# USB-C.net
KiCad netlist of a schematic drawn in Altium Designer
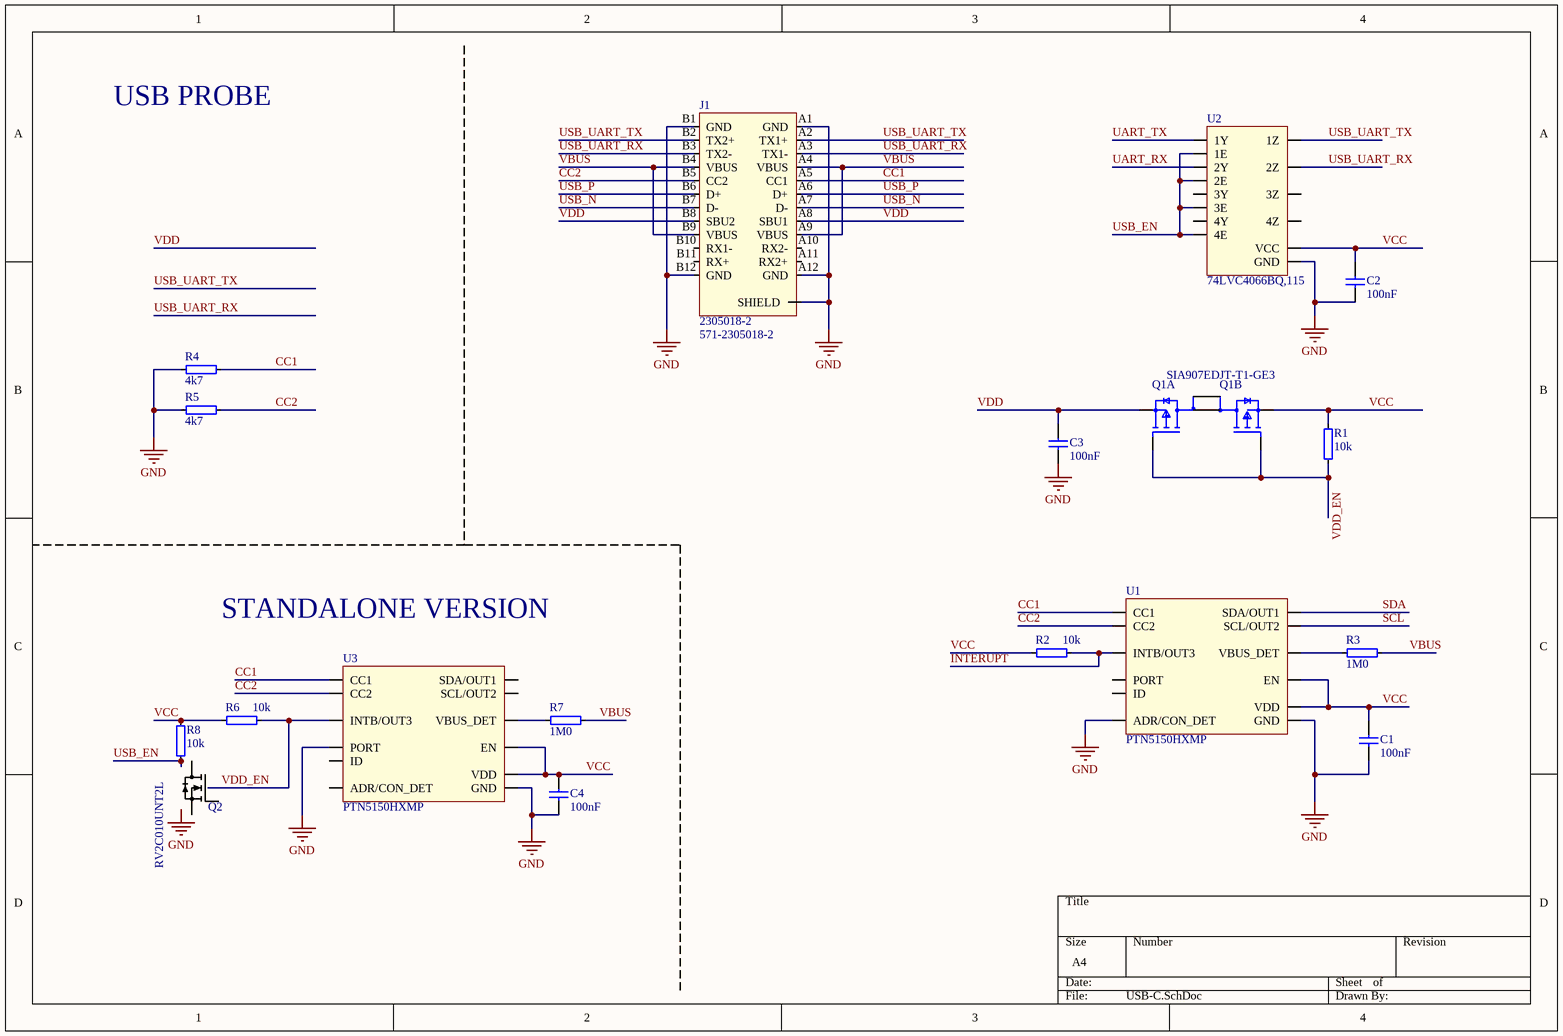
[diagram p0: USB-C.SchDoc]

(export (version "E")
  (design (tool "Eeschema 10.0.6"))
  (components
    (comp (ref "C1")
      (value "100nF")
      (footprint "CAPC0603X03L_C")
      (description "Capacitor, X5R, ±10%")
      (fields (field (name "PART NUMBER") "C0201-100n") (field (name "MANUFACTURER") "N.A."))
      (libsource (lib "main") (part "C0201-100n"))
    )
    (comp (ref "C2")
      (value "100nF")
      (footprint "CAPC0603X03L_C")
      (description "Capacitor, X5R, ±10%")
      (fields (field (name "PART NUMBER") "C0201-100n") (field (name "MANUFACTURER") "N.A."))
      (libsource (lib "main") (part "C0201-100n"))
    )
    (comp (ref "C3")
      (value "100nF")
      (footprint "CAPC0603X03L_C")
      (description "Capacitor, X5R, ±10%")
      (fields (field (name "PART NUMBER") "C0201-100n") (field (name "MANUFACTURER") "N.A."))
      (libsource (lib "main") (part "C0201-100n"))
    )
    (comp (ref "C4")
      (value "100nF")
      (footprint "CAPC0603X03L_C")
      (description "Capacitor, X5R, ±10%")
      (fields (field (name "PART NUMBER") "C0201-100n") (field (name "MANUFACTURER") "N.A."))
      (libsource (lib "main") (part "C0201-100n"))
    )
    (comp (ref "J1")
      (value "2305018-2")
      (footprint "2305018-2")
      (description "Usb 3.1 Type C, 10GBPS, Receptacle, Rigusb Connectors Usb Type C, Rec IPX8 on Board Dual SMT")
      (fields
        (field (name "MANUFACTURER") "TE Connectivity AMP")
        (field (name "SUPPLIER PART NUMBER 1") "571-2305018-2")
      )
      (libsource (lib "Schlib1") (part "2305018-2"))
    )
    (comp (ref "Q1")
      (value "SIA907EDJT-T1-GE3")
      (footprint "FP-C-07431-DUAL-MFG")
      (description "SiA907EDJT Series Dual P Channel 20 V 0.057 Ohm 7.8 W Mosfet - PowerPAK SC-70-6L")
      (fields (field (name "MANUFACTURER") "Vishay Siliconix"))
      (libsource (lib "Schlib1") (part "SIA907EDJT-T1-GE3"))
    )
    (comp (ref "Q2")
      (value "RV2C010UNT2L")
      (footprint "DFN65P100X40-3L")
      (description "MOSFET Transistor, N Channel, 1 A, 20 V, 0.34 ohm, 4.5 V, 1 V RoHS Compliant: Yes")
      (fields (field (name "MANUFACTURER") "Rohm"))
      (libsource (lib "Schlib1") (part "RV2C010UNT2L"))
    )
    (comp (ref "R1")
      (value "10k")
      (footprint "RESC0603X03L_C")
      (description "Resistor, ±1%, 0.05W")
      (fields (field (name "PART NUMBER") "R0201-10k") (field (name "MANUFACTURER") "N.A."))
      (libsource (lib "main") (part "R0201-10k"))
    )
    (comp (ref "R2")
      (value "10k")
      (footprint "RESC0603X03L_C")
      (description "Resistor, ±1%, 0.05W")
      (fields (field (name "PART NUMBER") "R0201-10k") (field (name "MANUFACTURER") "N.A."))
      (libsource (lib "main") (part "R0201-10k"))
    )
    (comp (ref "R3")
      (value "1M0")
      (footprint "RESC0603X03L_C")
      (description "Resistor, ±1%, 0.05W")
      (fields (field (name "PART NUMBER") "R0201-1M0") (field (name "MANUFACTURER") "N.A."))
      (libsource (lib "main") (part "R0201-1M0"))
    )
    (comp (ref "R4")
      (value "4k7")
      (footprint "RESC0603X03L_C")
      (description "Resistor, ±1%, 0.05W")
      (fields (field (name "PART NUMBER") "R0201-4k7") (field (name "MANUFACTURER") "N.A."))
      (libsource (lib "main") (part "R0201-4k7"))
    )
    (comp (ref "R5")
      (value "4k7")
      (footprint "RESC0603X03L_C")
      (description "Resistor, ±1%, 0.05W")
      (fields (field (name "PART NUMBER") "R0201-4k7") (field (name "MANUFACTURER") "N.A."))
      (libsource (lib "main") (part "R0201-4k7"))
    )
    (comp (ref "R6")
      (value "10k")
      (footprint "RESC0603X03L_C")
      (description "Resistor, ±1%, 0.05W")
      (fields (field (name "PART NUMBER") "R0201-10k") (field (name "MANUFACTURER") "N.A."))
      (libsource (lib "main") (part "R0201-10k"))
    )
    (comp (ref "R7")
      (value "1M0")
      (footprint "RESC0603X03L_C")
      (description "Resistor, ±1%, 0.05W")
      (fields (field (name "PART NUMBER") "R0201-1M0") (field (name "MANUFACTURER") "N.A."))
      (libsource (lib "main") (part "R0201-1M0"))
    )
    (comp (ref "R8")
      (value "10k")
      (footprint "RESC0603X03L_C")
      (description "Resistor, ±1%, 0.05W")
      (fields (field (name "PART NUMBER") "R0201-10k") (field (name "MANUFACTURER") "N.A."))
      (libsource (lib "main") (part "R0201-10k"))
    )
    (comp (ref "U1")
      (value "PTN5150HXMP")
      (footprint "PTN5150HXMP")
      (description "Usb Interface IC PTN5150HX/X2QFN12/REEL 13\" Q2/")
      (fields (field (name "MANUFACTURER") "NXP Semiconductors"))
      (libsource (lib "Schlib1") (part "PTN5150HXMP"))
    )
    (comp (ref "U2")
      (value "74LVC4066BQ,115")
      (footprint "74LVC4066BQ,115")
      (description "74LVC Series 5.5 V Quad Bilateral Switch - DHVQFN-14")
      (fields (field (name "MANUFACTURER") "Nexperia"))
      (libsource (lib "Schlib1") (part "74LVC4066BQ,115"))
    )
    (comp (ref "U3")
      (value "PTN5150HXMP")
      (footprint "PTN5150HXMP")
      (description "Usb Interface IC PTN5150HX/X2QFN12/REEL 13\" Q2/")
      (fields (field (name "MANUFACTURER") "NXP Semiconductors"))
      (libsource (lib "Schlib1") (part "PTN5150HXMP"))
    )
  )
  (nets
    (net (code "1") (name "/CC1") (class "Default")
      (node (ref "J1") (pin "A5") (pinfunction "CC1_A5") (pintype "passive"))
      (node (ref "R4") (pin "2") (pinfunction "2_2") (pintype "passive"))
      (node (ref "U1") (pin "P1") (pinfunction "CC1_P1") (pintype "passive"))
      (node (ref "U3") (pin "P1") (pinfunction "CC1_P1") (pintype "passive"))
    )
    (net (code "2") (name "/CC2") (class "Default")
      (node (ref "J1") (pin "B5") (pinfunction "CC2_B5") (pintype "passive"))
      (node (ref "R5") (pin "2") (pinfunction "2_2") (pintype "passive"))
      (node (ref "U1") (pin "P2") (pinfunction "CC2_P2") (pintype "passive"))
      (node (ref "U3") (pin "P2") (pinfunction "CC2_P2") (pintype "passive"))
    )
    (net (code "3") (name "/INTERUPT") (class "Default")
      (node (ref "R2") (pin "2") (pinfunction "2_2") (pintype "passive"))
      (node (ref "U1") (pin "P6") (pinfunction "INTB/OUT3_P6") (pintype "passive"))
    )
    (net (code "4") (name "/SCL") (class "Default")
      (node (ref "U1") (pin "P8") (pinfunction "SCL/OUT2_P8") (pintype "passive"))
    )
    (net (code "5") (name "/SDA") (class "Default")
      (node (ref "U1") (pin "P7") (pinfunction "SDA/OUT1_P7") (pintype "passive"))
    )
    (net (code "6") (name "/UART_RX") (class "Default")
      (node (ref "U2") (pin "P4") (pinfunction "2Y_P4") (pintype "passive"))
    )
    (net (code "7") (name "/UART_TX") (class "Default")
      (node (ref "U2") (pin "P1") (pinfunction "1Y_P1") (pintype "passive"))
    )
    (net (code "8") (name "/USB_EN") (class "Default")
      (node (ref "R8") (pin "1") (pinfunction "1_1") (pintype "passive"))
      (node (ref "U2") (pin "P12") (pinfunction "4E_P12") (pintype "passive"))
      (node (ref "U2") (pin "P13") (pinfunction "1E_P13") (pintype "passive"))
      (node (ref "U2") (pin "P5") (pinfunction "2E_P5") (pintype "passive"))
      (node (ref "U2") (pin "P6") (pinfunction "3E_P6") (pintype "passive"))
    )
    (net (code "9") (name "/USB_N") (class "Default")
      (node (ref "J1") (pin "A7") (pinfunction "D-_A7") (pintype "passive"))
      (node (ref "J1") (pin "B7") (pinfunction "D-_B7") (pintype "passive"))
    )
    (net (code "10") (name "/USB_P") (class "Default")
      (node (ref "J1") (pin "A6") (pinfunction "D+_A6") (pintype "passive"))
      (node (ref "J1") (pin "B6") (pinfunction "D+_B6") (pintype "passive"))
    )
    (net (code "11") (name "/USB_UART_RX") (class "Default")
      (node (ref "J1") (pin "A3") (pinfunction "TX1-_A3") (pintype "passive"))
      (node (ref "J1") (pin "B3") (pinfunction "TX2-_B3") (pintype "passive"))
      (node (ref "U2") (pin "P3") (pinfunction "2Z_P3") (pintype "passive"))
    )
    (net (code "12") (name "/USB_UART_TX") (class "Default")
      (node (ref "J1") (pin "A2") (pinfunction "TX1+_A2") (pintype "passive"))
      (node (ref "J1") (pin "B2") (pinfunction "TX2+_B2") (pintype "passive"))
      (node (ref "U2") (pin "P2") (pinfunction "1Z_P2") (pintype "passive"))
    )
    (net (code "13") (name "/VBUS") (class "Default")
      (node (ref "J1") (pin "A4") (pinfunction "VBUS_A4") (pintype "passive"))
      (node (ref "J1") (pin "A9") (pinfunction "VBUS_A9") (pintype "passive"))
      (node (ref "J1") (pin "B4") (pinfunction "VBUS_B4") (pintype "passive"))
      (node (ref "J1") (pin "B9") (pinfunction "VBUS_B9") (pintype "passive"))
      (node (ref "R3") (pin "2") (pinfunction "2_2") (pintype "passive"))
      (node (ref "R7") (pin "2") (pinfunction "2_2") (pintype "passive"))
    )
    (net (code "14") (name "/VCC") (class "Default")
      (node (ref "C1") (pin "2") (pinfunction "2_2") (pintype "passive"))
      (node (ref "C2") (pin "2") (pinfunction "2_2") (pintype "passive"))
      (node (ref "C4") (pin "2") (pinfunction "2_2") (pintype "passive"))
      (node (ref "Q1") (pin "4") (pinfunction "S2_4") (pintype "passive"))
      (node (ref "R1") (pin "2") (pinfunction "2_2") (pintype "passive"))
      (node (ref "R2") (pin "1") (pinfunction "1_1") (pintype "passive"))
      (node (ref "R6") (pin "1") (pinfunction "1_1") (pintype "passive"))
      (node (ref "R8") (pin "2") (pinfunction "2_2") (pintype "passive"))
      (node (ref "U1") (pin "P11") (pinfunction "EN_P11") (pintype "passive"))
      (node (ref "U1") (pin "P12") (pinfunction "VDD_P12") (pintype "passive"))
      (node (ref "U2") (pin "P14") (pinfunction "VCC_P14") (pintype "passive"))
      (node (ref "U3") (pin "P11") (pinfunction "EN_P11") (pintype "passive"))
      (node (ref "U3") (pin "P12") (pinfunction "VDD_P12") (pintype "passive"))
    )
    (net (code "15") (name "/VDD") (class "Default")
      (node (ref "C3") (pin "2") (pinfunction "2_2") (pintype "passive"))
      (node (ref "J1") (pin "A8") (pinfunction "SBU1_A8") (pintype "passive"))
      (node (ref "J1") (pin "B8") (pinfunction "SBU2_B8") (pintype "passive"))
      (node (ref "Q1") (pin "1") (pinfunction "S1_1") (pintype "passive"))
    )
    (net (code "16") (name "/VDD_EN") (class "Default")
      (node (ref "Q1") (pin "2") (pinfunction "G1_2") (pintype "passive"))
      (node (ref "Q1") (pin "5") (pinfunction "G2_5") (pintype "passive"))
      (node (ref "R1") (pin "1") (pinfunction "1_1") (pintype "passive"))
      (node (ref "R6") (pin "2") (pinfunction "2_2") (pintype "passive"))
      (node (ref "U3") (pin "P6") (pinfunction "INTB/OUT3_P6") (pintype "passive"))
    )
    (net (code "17") (name "GND") (class "Default")
      (node (ref "C1") (pin "1") (pinfunction "1_1") (pintype "passive"))
      (node (ref "C2") (pin "1") (pinfunction "1_1") (pintype "passive"))
      (node (ref "C3") (pin "1") (pinfunction "1_1") (pintype "passive"))
      (node (ref "C4") (pin "1") (pinfunction "1_1") (pintype "passive"))
      (node (ref "J1") (pin "A1") (pinfunction "GND_A1") (pintype "passive"))
      (node (ref "J1") (pin "A12") (pinfunction "GND_A12") (pintype "passive"))
      (node (ref "J1") (pin "B1") (pinfunction "GND_B1") (pintype "passive"))
      (node (ref "J1") (pin "B12") (pinfunction "GND_B12") (pintype "passive"))
      (node (ref "J1") (pin "SH1") (pinfunction "SHIELD_SH1") (pintype "passive"))
      (node (ref "R4") (pin "1") (pinfunction "1_1") (pintype "passive"))
      (node (ref "R5") (pin "1") (pinfunction "1_1") (pintype "passive"))
      (node (ref "U1") (pin "P10") (pinfunction "GND_P10") (pintype "passive"))
      (node (ref "U1") (pin "P5") (pinfunction "ADR/CON_DET_P5") (pintype "passive"))
      (node (ref "U2") (pin "P7") (pinfunction "GND_P7") (pintype "passive"))
      (node (ref "U3") (pin "P10") (pinfunction "GND_P10") (pintype "passive"))
      (node (ref "U3") (pin "P3") (pinfunction "PORT_P3") (pintype "passive"))
    )
    (net (code "18") (name "Net-(Q1A-D1-Pad6)") (class "Default")
      (node (ref "Q1") (pin "3") (pinfunction "D2_3") (pintype "passive"))
      (node (ref "Q1") (pin "6") (pinfunction "D1_6") (pintype "passive"))
    )
    (net (code "19") (name "Net-(Q1A-D1-Pad7)") (class "Default")
      (node (ref "Q1") (pin "7") (pinfunction "D1_7") (pintype "passive"))
      (node (ref "Q1") (pin "8") (pinfunction "D2_8") (pintype "passive"))
    )
    (net (code "20") (name "Net-(U1-VBUS_DET)") (class "Default")
      (node (ref "R3") (pin "1") (pinfunction "1_1") (pintype "passive"))
      (node (ref "U1") (pin "P4") (pinfunction "VBUS_DET_P4") (pintype "passive"))
    )
    (net (code "21") (name "Net-(U3-VBUS_DET)") (class "Default")
      (node (ref "R7") (pin "1") (pinfunction "1_1") (pintype "passive"))
      (node (ref "U3") (pin "P4") (pinfunction "VBUS_DET_P4") (pintype "passive"))
    )
    (net (code "22") (name "unconnected-(J1-RX+-PadB11)") (class "Default")
      (node (ref "J1") (pin "B11") (pinfunction "RX+_B11") (pintype "passive"))
    )
    (net (code "23") (name "unconnected-(J1-RX1--PadB10)") (class "Default")
      (node (ref "J1") (pin "B10") (pinfunction "RX1-_B10") (pintype "passive"))
    )
    (net (code "24") (name "unconnected-(J1-RX2+-PadA11)") (class "Default")
      (node (ref "J1") (pin "A11") (pinfunction "RX2+_A11") (pintype "passive"))
    )
    (net (code "25") (name "unconnected-(J1-RX2--PadA10)") (class "Default")
      (node (ref "J1") (pin "A10") (pinfunction "RX2-_A10") (pintype "passive"))
    )
    (net (code "26") (name "unconnected-(Q2-D-Pad3)") (class "Default")
      (node (ref "Q2") (pin "3") (pinfunction "D_3") (pintype "passive"))
    )
    (net (code "27") (name "unconnected-(Q2-G-Pad1)") (class "Default")
      (node (ref "Q2") (pin "1") (pinfunction "G_1") (pintype "passive"))
    )
    (net (code "28") (name "unconnected-(Q2-S-Pad2)") (class "Default")
      (node (ref "Q2") (pin "2") (pinfunction "S_2") (pintype "passive"))
    )
    (net (code "29") (name "unconnected-(U1-ID-PadP9)") (class "Default")
      (node (ref "U1") (pin "P9") (pinfunction "ID_P9") (pintype "passive"))
    )
    (net (code "30") (name "unconnected-(U1-PORT-PadP3)") (class "Default")
      (node (ref "U1") (pin "P3") (pinfunction "PORT_P3") (pintype "passive"))
    )
    (net (code "31") (name "unconnected-(U2-3Y-PadP8)") (class "Default")
      (node (ref "U2") (pin "P8") (pinfunction "3Y_P8") (pintype "passive"))
    )
    (net (code "32") (name "unconnected-(U2-3Z-PadP9)") (class "Default")
      (node (ref "U2") (pin "P9") (pinfunction "3Z_P9") (pintype "passive"))
    )
    (net (code "33") (name "unconnected-(U2-4Y-PadP11)") (class "Default")
      (node (ref "U2") (pin "P11") (pinfunction "4Y_P11") (pintype "passive"))
    )
    (net (code "34") (name "unconnected-(U2-4Z-PadP10)") (class "Default")
      (node (ref "U2") (pin "P10") (pinfunction "4Z_P10") (pintype "passive"))
    )
    (net (code "35") (name "unconnected-(U3-ADR{slash}CON_DET-PadP5)") (class "Default")
      (node (ref "U3") (pin "P5") (pinfunction "ADR/CON_DET_P5") (pintype "passive"))
    )
    (net (code "36") (name "unconnected-(U3-ID-PadP9)") (class "Default")
      (node (ref "U3") (pin "P9") (pinfunction "ID_P9") (pintype "passive"))
    )
    (net (code "37") (name "unconnected-(U3-SCL{slash}OUT2-PadP8)") (class "Default")
      (node (ref "U3") (pin "P8") (pinfunction "SCL/OUT2_P8") (pintype "passive"))
    )
    (net (code "38") (name "unconnected-(U3-SDA{slash}OUT1-PadP7)") (class "Default")
      (node (ref "U3") (pin "P7") (pinfunction "SDA/OUT1_P7") (pintype "passive"))
    )
  )
)
